# GNNS_Module.net
KiCad netlist of a schematic drawn in Altium Designer
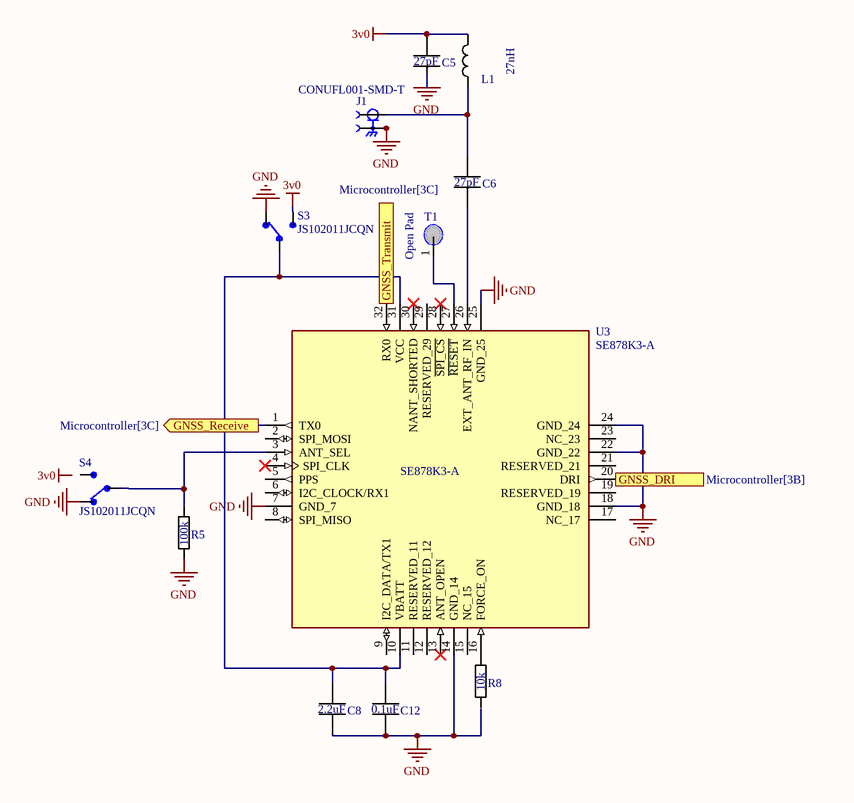
[diagram p0: GNNS_Module.SchDoc]

(export (version "E")
  (design (tool "Eeschema 10.0.6"))
  (components
    (comp (ref "C5")
      (value "27pF")
      (footprint "0603 (Capacitor)")
      (description "Capacitor 12pF 0603 +/-2%")
      (fields
        (field (name "MANUFACTURER") "Murata")
        (field (name "MANUFACTURER PARTNO") "GQM1875C2E120GB12D")
      )
      (libsource (lib "Passives") (part "C-p-012.000-2-0603"))
    )
    (comp (ref "C6")
      (value "27pF")
      (footprint "0603 (Capacitor)")
      (description "Capacitor 12pF 0603 +/-2%")
      (fields
        (field (name "MANUFACTURER") "Murata")
        (field (name "MANUFACTURER PARTNO") "GQM1875C2E120GB12D")
      )
      (libsource (lib "Passives") (part "C-p-012.000-2-0603"))
    )
    (comp (ref "C8")
      (value "2.2uF")
      (footprint "0603 (Capacitor)")
      (description "Capacitor 2.2uF 0603 +/-5%")
      (fields
        (field (name "MANUFACTURER") "Murata")
        (field (name "MANUFACTURER PARTNO") "GRM1885C1H103JA01D")
      )
      (libsource (lib "Passives") (part "C-n-010.000-5-0603"))
    )
    (comp (ref "C12")
      (value "0.1uF")
      (footprint "0603 (Capacitor)")
      (description "Capacitor 0.1uF 0603 +/-5%")
      (fields
        (field (name "MANUFACTURER") "Murata")
        (field (name "MANUFACTURER PARTNO") "GCM1885C2A102JA16D")
      )
      (libsource (lib "Passives") (part "C-n-001.000-5-0603"))
    )
    (comp (ref "J1")
      (value "CONUFL001-SMD-T")
      (footprint "Antenna- CONUFL001-SMD-T")
      (libsource (lib "CONUFL001-SMD-T") (part "CONUFL001-SMD-T"))
    )
    (comp (ref "L1")
      (value "27nH")
      (footprint "PcbLib:4426R-9")
      (description "Inductor 27nH 0402 +/-5%")
      (fields (field (name "MANUFACTURER") "Murata") (field (name "MANUFACTURER PARTNO") "LQG15HS27NJ02D"))
      (libsource (lib "Passives") (part "L-n-027.000-5-0402"))
    )
    (comp (ref "R5")
      (value "100k")
      (footprint "0603 (Resistor)")
      (description "Resistor 100k 0603 +/-1%")
      (fields
        (field (name "MANUFACTURER") "Vishay Dale")
        (field (name "MANUFACTURER PARTNO") "CRCW0603100KFKEAHP")
      )
      (libsource (lib "Passives") (part "R-k-100.000-1-0603"))
    )
    (comp (ref "R8")
      (value "10k")
      (footprint "0603 (Resistor)")
      (description "Resistor 10k 0603 +/-1%")
      (fields
        (field (name "MANUFACTURER") "Vishay Dale")
        (field (name "MANUFACTURER PARTNO") "CRCW060310K0FKEAHP")
      )
      (libsource (lib "Passives") (part "R-k-010.000-1-0603"))
    )
    (comp (ref "S3")
      (value "JS102011JCQN")
      (footprint "SW_JS102011JCQN")
      (description "Switch Slide Spdt 300ma 6v")
      (libsource (lib "JS102011JCQN") (part "JS102011JCQN"))
    )
    (comp (ref "S4")
      (value "JS102011JCQN")
      (footprint "SW_JS102011JCQN")
      (description "Switch Slide Spdt 300ma 6v")
      (libsource (lib "JS102011JCQN") (part "JS102011JCQN"))
    )
    (comp (ref "T1") (value "Open Pad") (footprint "Open Pad") (libsource (lib "Schlib") (part "Open Pad")))
    (comp (ref "U3")
      (value "SE878K3-A")
      (footprint "GNSS Module")
      (description "GNSS L1 Antenna module (GPS, Galileo, Glonass, BeiDou)")
      (fields (field (name "MF") "Telit"))
      (libsource (lib "SE878K3-A") (part "SE878K3-A"))
    )
  )
  (nets
    (net (code "1") (name "/GNSS_DRI") (class "Default")
      (node (ref "U3") (pin "20") (pinfunction "DRI_20") (pintype "output"))
    )
    (net (code "2") (name "/GNSS_Receive") (class "Default")
      (node (ref "U3") (pin "1") (pinfunction "TX0_1") (pintype "output"))
    )
    (net (code "3") (name "/GNSS_Transmit") (class "Default")
      (node (ref "U3") (pin "32") (pinfunction "RX0_32") (pintype "input"))
    )
    (net (code "4") (name "3v0") (class "Default")
      (node (ref "C5") (pin "1") (pinfunction "1_1") (pintype "passive"))
      (node (ref "L1") (pin "1") (pinfunction "1_1") (pintype "passive"))
      (node (ref "S3") (pin "3") (pinfunction "3_3") (pintype "passive"))
    )
    (net (code "5") (name "GND") (class "Default")
      (node (ref "C12") (pin "2") (pinfunction "2_2") (pintype "passive"))
      (node (ref "C5") (pin "2") (pinfunction "2_2") (pintype "passive"))
      (node (ref "C8") (pin "2") (pinfunction "2_2") (pintype "passive"))
      (node (ref "J1") (pin "2") (pinfunction "2_2") (pintype "passive"))
      (node (ref "J1") (pin "3") (pinfunction "2_3") (pintype "passive"))
      (node (ref "R5") (pin "2") (pinfunction "2_2") (pintype "passive"))
      (node (ref "S3") (pin "1") (pinfunction "1_1") (pintype "passive"))
      (node (ref "S4") (pin "1") (pinfunction "1_1") (pintype "passive"))
      (node (ref "U3") (pin "14") (pinfunction "GND_14_14") (pintype "power_in"))
      (node (ref "U3") (pin "18") (pinfunction "GND_18_18") (pintype "power_in"))
      (node (ref "U3") (pin "22") (pinfunction "GND_22_22") (pintype "power_in"))
      (node (ref "U3") (pin "24") (pinfunction "GND_24_24") (pintype "power_in"))
      (node (ref "U3") (pin "25") (pinfunction "GND_25_25") (pintype "power_in"))
      (node (ref "U3") (pin "7") (pinfunction "GND_7_7") (pintype "power_in"))
    )
    (net (code "6") (name "Net-(C6-Pad1)") (class "Default")
      (node (ref "C6") (pin "1") (pinfunction "1_1") (pintype "passive"))
      (node (ref "J1") (pin "1") (pinfunction "1_1") (pintype "passive"))
      (node (ref "L1") (pin "2") (pinfunction "2_2") (pintype "passive"))
    )
    (net (code "7") (name "Net-(U3-ANT_SEL)") (class "Default")
      (node (ref "R5") (pin "1") (pinfunction "1_1") (pintype "passive"))
      (node (ref "S4") (pin "2") (pinfunction "2_2") (pintype "passive"))
      (node (ref "U3") (pin "3") (pinfunction "ANT_SEL_3") (pintype "input"))
    )
    (net (code "8") (name "Net-(U3-EXT_ANT_RF_IN)") (class "Default")
      (node (ref "C6") (pin "2") (pinfunction "2_2") (pintype "passive"))
      (node (ref "U3") (pin "26") (pinfunction "EXT_ANT_RF_IN_26") (pintype "input"))
    )
    (net (code "9") (name "Net-(U3-FORCE_ON)") (class "Default")
      (node (ref "R8") (pin "1") (pinfunction "1_1") (pintype "passive"))
      (node (ref "U3") (pin "16") (pinfunction "FORCE_ON_16") (pintype "input"))
    )
    (net (code "10") (name "Net-(U3-VBATT)") (class "Default")
      (node (ref "C12") (pin "1") (pinfunction "1_1") (pintype "passive"))
      (node (ref "C8") (pin "1") (pinfunction "1_1") (pintype "passive"))
      (node (ref "S3") (pin "2") (pinfunction "2_2") (pintype "passive"))
      (node (ref "U3") (pin "10") (pinfunction "VBATT_10") (pintype "power_in"))
      (node (ref "U3") (pin "31") (pinfunction "VCC_31") (pintype "power_in"))
    )
    (net (code "11") (name "Net-(U3-~{RESET})") (class "Default")
      (node (ref "T1") (pin "1") (pintype "passive"))
      (node (ref "U3") (pin "27") (pinfunction "~{RESET}_27") (pintype "input"))
    )
    (net (code "12") (name "unconnected-(R8-Pad2)") (class "Default")
      (node (ref "R8") (pin "2") (pinfunction "2_2") (pintype "passive"))
    )
    (net (code "13") (name "unconnected-(S4-Pad3)") (class "Default")
      (node (ref "S4") (pin "3") (pinfunction "3_3") (pintype "passive"))
    )
    (net (code "14") (name "unconnected-(U3-ANT_OPEN-Pad13)") (class "Default")
      (node (ref "U3") (pin "13") (pinfunction "ANT_OPEN_13") (pintype "input+no_connect"))
    )
    (net (code "15") (name "unconnected-(U3-I2C_CLOCK{slash}RX1-Pad6)") (class "Default")
      (node (ref "U3") (pin "6") (pinfunction "I2C_CLOCK/RX1_6") (pintype "bidirectional"))
    )
    (net (code "16") (name "unconnected-(U3-I2C_DATA{slash}TX1-Pad9)") (class "Default")
      (node (ref "U3") (pin "9") (pinfunction "I2C_DATA/TX1_9") (pintype "bidirectional"))
    )
    (net (code "17") (name "unconnected-(U3-NANT_SHORTED-Pad30)") (class "Default")
      (node (ref "U3") (pin "30") (pinfunction "NANT_SHORTED_30") (pintype "input+no_connect"))
    )
    (net (code "18") (name "unconnected-(U3-NC_15-Pad15)") (class "Default")
      (node (ref "U3") (pin "15") (pinfunction "NC_15_15") (pintype "passive"))
    )
    (net (code "19") (name "unconnected-(U3-NC_17-Pad17)") (class "Default")
      (node (ref "U3") (pin "17") (pinfunction "NC_17_17") (pintype "passive"))
    )
    (net (code "20") (name "unconnected-(U3-NC_23-Pad23)") (class "Default")
      (node (ref "U3") (pin "23") (pinfunction "NC_23_23") (pintype "passive"))
    )
    (net (code "21") (name "unconnected-(U3-PPS-Pad5)") (class "Default")
      (node (ref "U3") (pin "5") (pinfunction "PPS_5") (pintype "output"))
    )
    (net (code "22") (name "unconnected-(U3-RESERVED_11-Pad11)") (class "Default")
      (node (ref "U3") (pin "11") (pinfunction "RESERVED_11_11") (pintype "passive"))
    )
    (net (code "23") (name "unconnected-(U3-RESERVED_12-Pad12)") (class "Default")
      (node (ref "U3") (pin "12") (pinfunction "RESERVED_12_12") (pintype "passive"))
    )
    (net (code "24") (name "unconnected-(U3-RESERVED_19-Pad19)") (class "Default")
      (node (ref "U3") (pin "19") (pinfunction "RESERVED_19_19") (pintype "passive"))
    )
    (net (code "25") (name "unconnected-(U3-RESERVED_21-Pad21)") (class "Default")
      (node (ref "U3") (pin "21") (pinfunction "RESERVED_21_21") (pintype "passive"))
    )
    (net (code "26") (name "unconnected-(U3-RESERVED_29-Pad29)") (class "Default")
      (node (ref "U3") (pin "29") (pinfunction "RESERVED_29_29") (pintype "passive"))
    )
    (net (code "27") (name "unconnected-(U3-SPI_CLK-Pad4)") (class "Default")
      (node (ref "U3") (pin "4") (pinfunction "SPI_CLK_4") (pintype "input+no_connect"))
    )
    (net (code "28") (name "unconnected-(U3-SPI_MISO-Pad8)") (class "Default")
      (node (ref "U3") (pin "8") (pinfunction "SPI_MISO_8") (pintype "bidirectional"))
    )
    (net (code "29") (name "unconnected-(U3-SPI_MOSI-Pad2)") (class "Default")
      (node (ref "U3") (pin "2") (pinfunction "SPI_MOSI_2") (pintype "bidirectional"))
    )
    (net (code "30") (name "unconnected-(U3-~{SPI_CS}-Pad28)") (class "Default")
      (node (ref "U3") (pin "28") (pinfunction "~{SPI_CS}_28") (pintype "input+no_connect"))
    )
  )
)
